# DISCHARGE.net
KiCad netlist of a schematic drawn in EAGLE
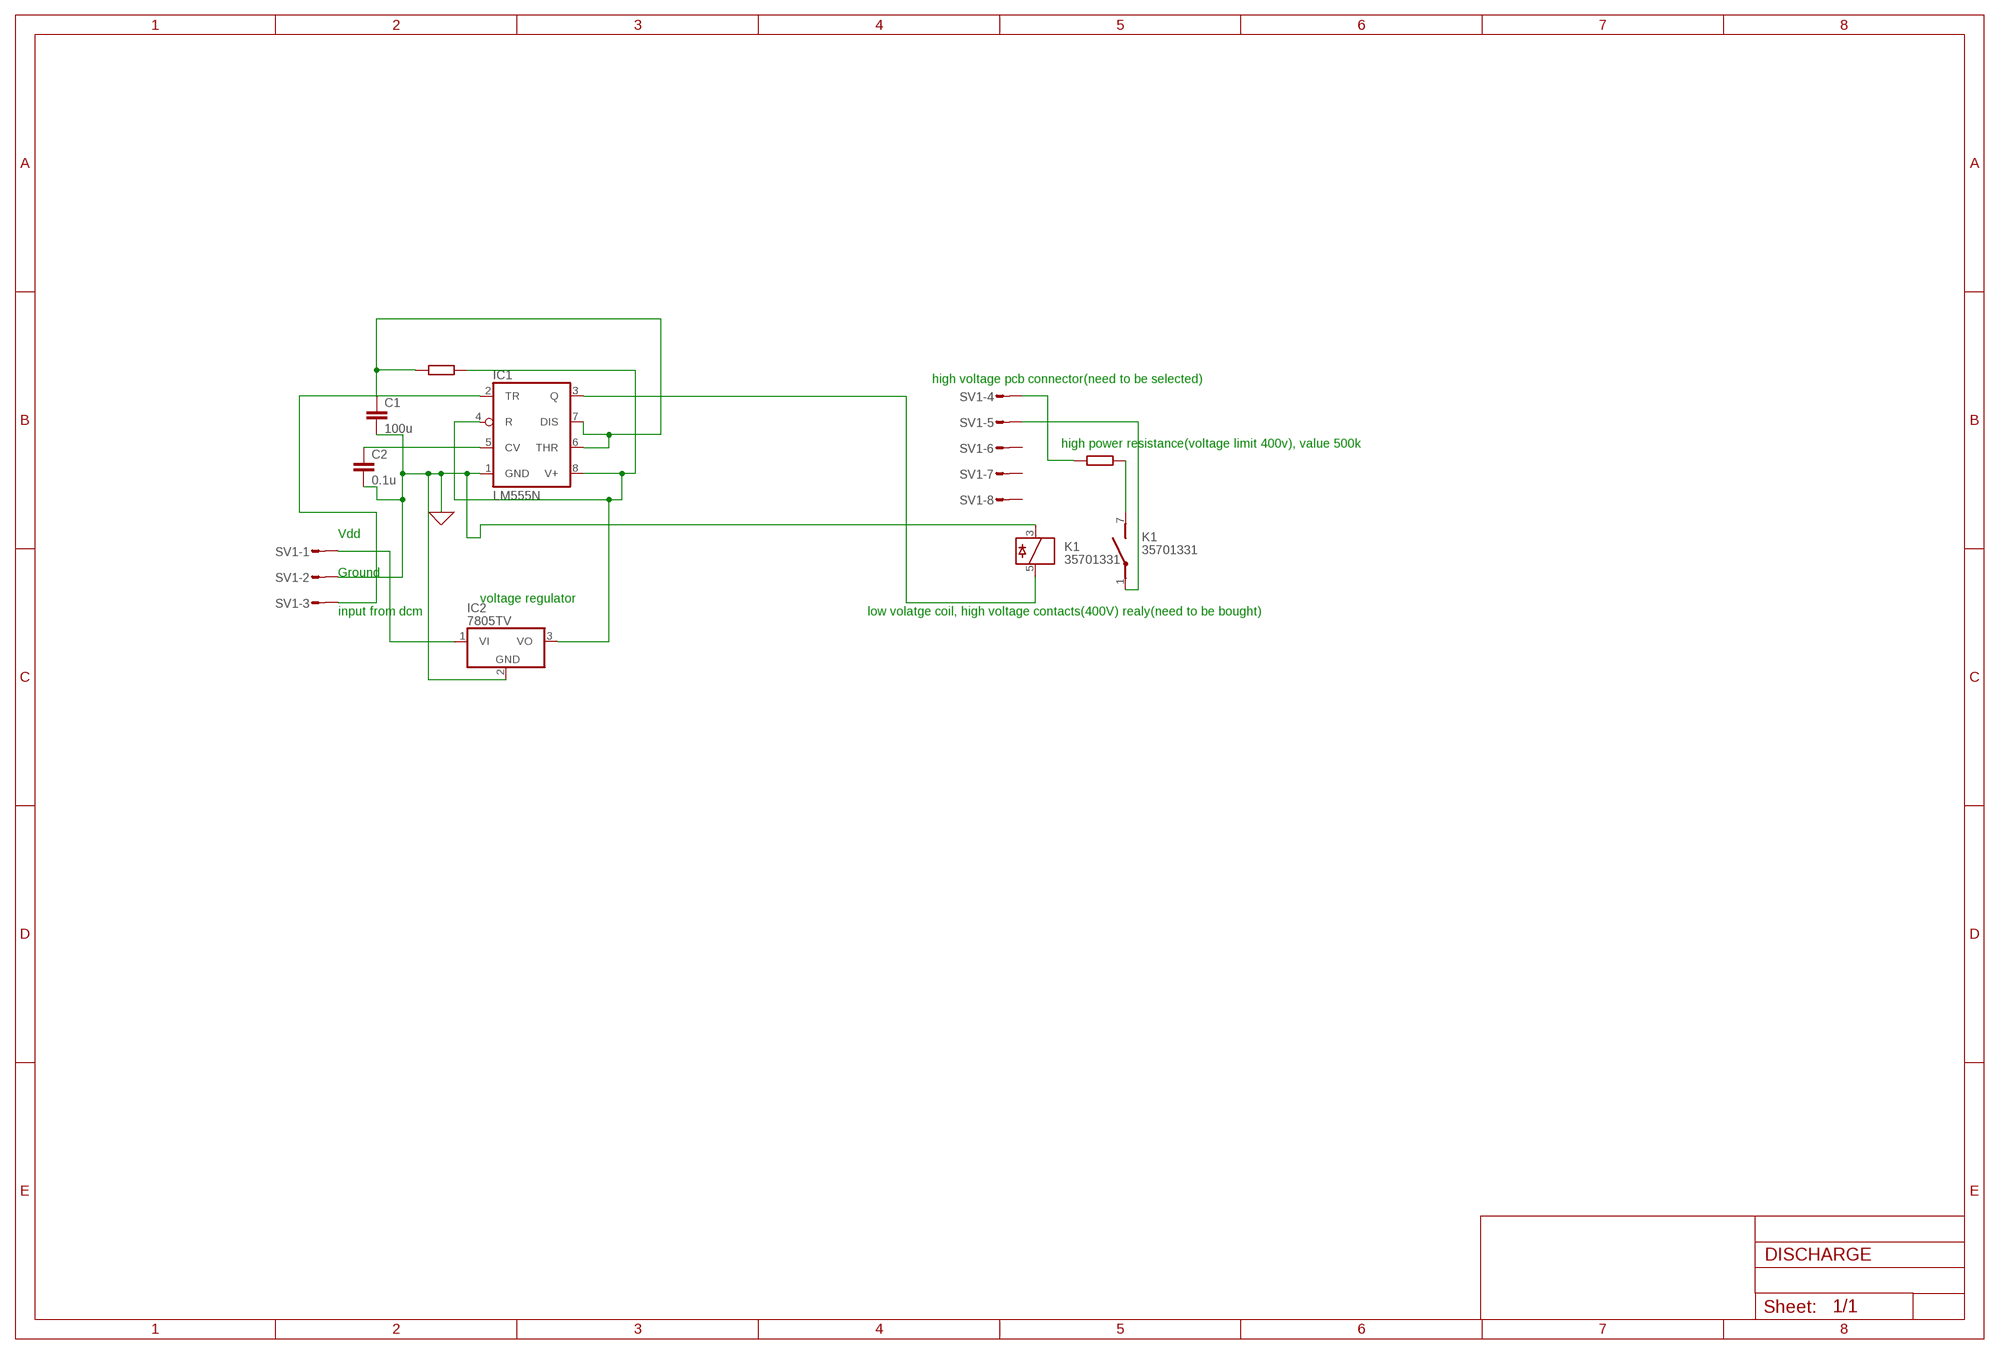
[diagram p0: schematic, sheet 1]

(export (version "E")
  (design (tool "Eeschema 10.0.6"))
  (components
    (comp (ref "C1")
      (value "100u")
      (footprint "eagle-import:C2.5-3")
      (libsource (lib "eagle-import") (part "C2,5-3"))
    )
    (comp (ref "C2")
      (value "0.1u")
      (footprint "eagle-import:C2.5-3")
      (libsource (lib "eagle-import") (part "C2,5-3"))
    )
    (comp (ref "IC1")
      (value "LM555N")
      (footprint "eagle-import:DIL08")
      (libsource (lib "eagle-import") (part "555NLM"))
    )
    (comp (ref "IC2")
      (value "7805TV")
      (footprint "eagle-import:TO220V")
      (libsource (lib "eagle-import") (part "78TV05"))
    )
    (comp (ref "K1")
      (value "35701331")
      (footprint "eagle-import:REED")
      (libsource (lib "eagle-import") (part "35701331"))
    )
    (comp (ref "SV1")
      (value "MT6-8")
      (footprint "eagle-import:MT6-8")
      (libsource (lib "eagle-import") (part "MT6-8"))
    )
  )
  (nets
    (net (code "1") (name "GND") (class "Default")
      (node (ref "C1") (pin "2") (pinfunction "2_2") (pintype "passive"))
      (node (ref "C2") (pin "2") (pinfunction "2_2") (pintype "passive"))
      (node (ref "IC1") (pin "1") (pinfunction "GND_1") (pintype "power_in"))
      (node (ref "IC2") (pin "2") (pinfunction "GND_2") (pintype "passive"))
      (node (ref "K1") (pin "3") (pinfunction "3_3") (pintype "passive"))
      (node (ref "SV1") (pin "2") (pinfunction "S_2") (pintype "passive"))
    )
    (net (code "2") (name "Net-(IC1-CV)") (class "Default")
      (node (ref "C2") (pin "1") (pinfunction "1_1") (pintype "passive"))
      (node (ref "IC1") (pin "5") (pinfunction "CV_5") (pintype "input"))
    )
    (net (code "3") (name "Net-(IC1-DIS)") (class "Default")
      (node (ref "C1") (pin "1") (pinfunction "1_1") (pintype "passive"))
      (node (ref "IC1") (pin "6") (pinfunction "THR_6") (pintype "input"))
      (node (ref "IC1") (pin "7") (pinfunction "DIS_7") (pintype "input"))
    )
    (net (code "4") (name "Net-(IC1-Q)") (class "Default")
      (node (ref "IC1") (pin "3") (pinfunction "Q_3") (pintype "output"))
      (node (ref "K1") (pin "5") (pinfunction "5_5") (pintype "passive"))
    )
    (net (code "5") (name "Net-(IC1-R)") (class "Default")
      (node (ref "IC1") (pin "4") (pinfunction "R_4") (pintype "input"))
      (node (ref "IC1") (pin "8") (pinfunction "V+_8") (pintype "power_in"))
      (node (ref "IC2") (pin "3") (pinfunction "VO_3") (pintype "passive"))
    )
    (net (code "6") (name "Net-(IC1-TR)") (class "Default")
      (node (ref "IC1") (pin "2") (pinfunction "TR_2") (pintype "input"))
      (node (ref "SV1") (pin "3") (pinfunction "S_3") (pintype "passive"))
    )
    (net (code "7") (name "Net-(IC2-VI)") (class "Default")
      (node (ref "IC2") (pin "1") (pinfunction "VI_1") (pintype "input"))
      (node (ref "SV1") (pin "1") (pinfunction "S_1") (pintype "passive"))
    )
    (net (code "8") (name "Net-(K1B-P)") (class "Default")
      (node (ref "K1") (pin "1") (pinfunction "P_1") (pintype "passive"))
      (node (ref "SV1") (pin "5") (pinfunction "S_5") (pintype "passive"))
    )
    (net (code "9") (name "unconnected-(K1B-S-Pad7)") (class "Default")
      (node (ref "K1") (pin "7") (pinfunction "S_7") (pintype "passive"))
    )
    (net (code "10") (name "unconnected-(SV1D-S-Pad4)") (class "Default")
      (node (ref "SV1") (pin "4") (pinfunction "S_4") (pintype "passive"))
    )
    (net (code "11") (name "unconnected-(SV1F-S-Pad6)") (class "Default")
      (node (ref "SV1") (pin "6") (pinfunction "S_6") (pintype "passive"))
    )
    (net (code "12") (name "unconnected-(SV1G-S-Pad7)") (class "Default")
      (node (ref "SV1") (pin "7") (pinfunction "S_7") (pintype "passive"))
    )
    (net (code "13") (name "unconnected-(SV1H-S-Pad8)") (class "Default")
      (node (ref "SV1") (pin "8") (pinfunction "S_8") (pintype "passive"))
    )
  )
)
